# Mini51.net
KiCad netlist of a schematic drawn in Altium Designer
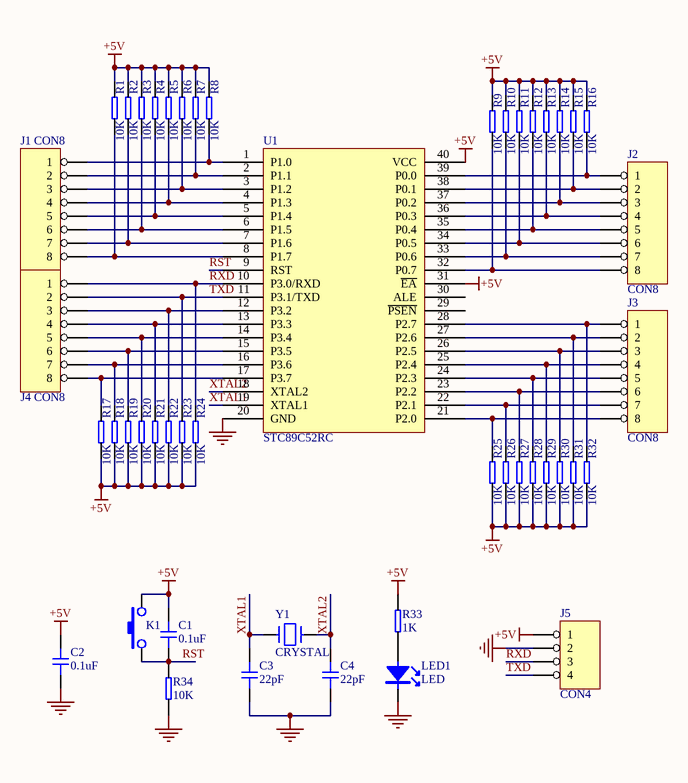
[diagram p0: Mini51.SchDoc]

(export (version "E")
  (design (tool "Eeschema 10.0.6"))
  (components
    (comp (ref "C1") (value "0.1uF") (footprint "0805") (libsource (lib "Mini51Lib") (part "CAP")))
    (comp (ref "C2") (value "0.1uF") (footprint "0805") (libsource (lib "Mini51Lib") (part "CAP")))
    (comp (ref "C3") (value "22pF") (footprint "0805") (libsource (lib "Mini51Lib") (part "CAP")))
    (comp (ref "C4") (value "22pF") (footprint "0805") (libsource (lib "Mini51Lib") (part "CAP")))
    (comp (ref "J1")
      (value "CON8")
      (footprint "SIP8")
      (description "Connector 8p")
      (libsource (lib "") (part "CON8_1"))
    )
    (comp (ref "J2")
      (value "CON8")
      (footprint "SIP8")
      (description "Connector 8p")
      (libsource (lib "Mini51Lib") (part "CON8"))
    )
    (comp (ref "J3")
      (value "CON8")
      (footprint "SIP8")
      (description "Connector 8p")
      (libsource (lib "Mini51Lib") (part "CON8"))
    )
    (comp (ref "J4")
      (value "CON8")
      (footprint "SIP8")
      (description "Connector 8p")
      (libsource (lib "") (part "CON8_1"))
    )
    (comp (ref "J5") (value "CON4") (footprint "SIP4") (libsource (lib "Mini51Lib") (part "CON4")))
    (comp (ref "K1")
      (value "KEY")
      (footprint "KEY-6*6")
      (description "push-button")
      (libsource (lib "Mini51Lib") (part "KEY"))
    )
    (comp (ref "LED1")
      (value "LED")
      (footprint "0805LD")
      (description "Light-Emitting Diode")
      (libsource (lib "Mini51Lib") (part "LED"))
    )
    (comp (ref "R1") (value "10K") (footprint "0805") (libsource (lib "Mini51Lib") (part "RES")))
    (comp (ref "R2") (value "10K") (footprint "0805") (libsource (lib "Mini51Lib") (part "RES")))
    (comp (ref "R3") (value "10K") (footprint "0805") (libsource (lib "Mini51Lib") (part "RES")))
    (comp (ref "R4") (value "10K") (footprint "0805") (libsource (lib "Mini51Lib") (part "RES")))
    (comp (ref "R5") (value "10K") (footprint "0805") (libsource (lib "Mini51Lib") (part "RES")))
    (comp (ref "R6") (value "10K") (footprint "0805") (libsource (lib "Mini51Lib") (part "RES")))
    (comp (ref "R7") (value "10K") (footprint "0805") (libsource (lib "Mini51Lib") (part "RES")))
    (comp (ref "R8") (value "10K") (footprint "0805") (libsource (lib "Mini51Lib") (part "RES")))
    (comp (ref "R9") (value "10K") (footprint "0805") (libsource (lib "Mini51Lib") (part "RES")))
    (comp (ref "R10") (value "10K") (footprint "0805") (libsource (lib "Mini51Lib") (part "RES")))
    (comp (ref "R11") (value "10K") (footprint "0805") (libsource (lib "Mini51Lib") (part "RES")))
    (comp (ref "R12") (value "10K") (footprint "0805") (libsource (lib "Mini51Lib") (part "RES")))
    (comp (ref "R13") (value "10K") (footprint "0805") (libsource (lib "Mini51Lib") (part "RES")))
    (comp (ref "R14") (value "10K") (footprint "0805") (libsource (lib "Mini51Lib") (part "RES")))
    (comp (ref "R15") (value "10K") (footprint "0805") (libsource (lib "Mini51Lib") (part "RES")))
    (comp (ref "R16") (value "10K") (footprint "0805") (libsource (lib "Mini51Lib") (part "RES")))
    (comp (ref "R17") (value "10K") (footprint "0805") (libsource (lib "Mini51Lib") (part "RES")))
    (comp (ref "R18") (value "10K") (footprint "0805") (libsource (lib "Mini51Lib") (part "RES")))
    (comp (ref "R19") (value "10K") (footprint "0805") (libsource (lib "Mini51Lib") (part "RES")))
    (comp (ref "R20") (value "10K") (footprint "0805") (libsource (lib "Mini51Lib") (part "RES")))
    (comp (ref "R21") (value "10K") (footprint "0805") (libsource (lib "Mini51Lib") (part "RES")))
    (comp (ref "R22") (value "10K") (footprint "0805") (libsource (lib "Mini51Lib") (part "RES")))
    (comp (ref "R23") (value "10K") (footprint "0805") (libsource (lib "Mini51Lib") (part "RES")))
    (comp (ref "R24") (value "10K") (footprint "0805") (libsource (lib "Mini51Lib") (part "RES")))
    (comp (ref "R25") (value "10K") (footprint "0805") (libsource (lib "Mini51Lib") (part "RES")))
    (comp (ref "R26") (value "10K") (footprint "0805") (libsource (lib "Mini51Lib") (part "RES")))
    (comp (ref "R27") (value "10K") (footprint "0805") (libsource (lib "Mini51Lib") (part "RES")))
    (comp (ref "R28") (value "10K") (footprint "0805") (libsource (lib "Mini51Lib") (part "RES")))
    (comp (ref "R29") (value "10K") (footprint "0805") (libsource (lib "Mini51Lib") (part "RES")))
    (comp (ref "R30") (value "10K") (footprint "0805") (libsource (lib "Mini51Lib") (part "RES")))
    (comp (ref "R31") (value "10K") (footprint "0805") (libsource (lib "Mini51Lib") (part "RES")))
    (comp (ref "R32") (value "10K") (footprint "0805") (libsource (lib "Mini51Lib") (part "RES")))
    (comp (ref "R33") (value "1K") (footprint "0805") (libsource (lib "Mini51Lib") (part "RES")))
    (comp (ref "R34") (value "10K") (footprint "0805") (libsource (lib "Mini51Lib") (part "RES")))
    (comp (ref "U1") (value "STC89C52RC") (footprint "DIP40") (libsource (lib "Mini51Lib") (part "STC89C52")))
    (comp (ref "Y1")
      (value "CRYSTAL")
      (footprint "XTAL-2")
      (description "Crystal")
      (libsource (lib "Mini51Lib") (part "CRYSTAL"))
    )
  )
  (nets
    (net (code "1") (name "+5V") (class "Default")
      (node (ref "C1") (pin "2") (pinfunction "2_2") (pintype "passive"))
      (node (ref "C2") (pin "2") (pinfunction "2_2") (pintype "passive"))
      (node (ref "J5") (pin "1") (pinfunction "1_1") (pintype "passive"))
      (node (ref "K1") (pin "2") (pinfunction "2_2") (pintype "passive"))
      (node (ref "R1") (pin "2") (pinfunction "2_2") (pintype "passive"))
      (node (ref "R10") (pin "2") (pinfunction "2_2") (pintype "passive"))
      (node (ref "R11") (pin "2") (pinfunction "2_2") (pintype "passive"))
      (node (ref "R12") (pin "2") (pinfunction "2_2") (pintype "passive"))
      (node (ref "R13") (pin "2") (pinfunction "2_2") (pintype "passive"))
      (node (ref "R14") (pin "2") (pinfunction "2_2") (pintype "passive"))
      (node (ref "R15") (pin "2") (pinfunction "2_2") (pintype "passive"))
      (node (ref "R16") (pin "2") (pinfunction "2_2") (pintype "passive"))
      (node (ref "R17") (pin "1") (pinfunction "1_1") (pintype "passive"))
      (node (ref "R18") (pin "1") (pinfunction "1_1") (pintype "passive"))
      (node (ref "R19") (pin "1") (pinfunction "1_1") (pintype "passive"))
      (node (ref "R2") (pin "2") (pinfunction "2_2") (pintype "passive"))
      (node (ref "R20") (pin "1") (pinfunction "1_1") (pintype "passive"))
      (node (ref "R21") (pin "1") (pinfunction "1_1") (pintype "passive"))
      (node (ref "R22") (pin "1") (pinfunction "1_1") (pintype "passive"))
      (node (ref "R23") (pin "1") (pinfunction "1_1") (pintype "passive"))
      (node (ref "R24") (pin "1") (pinfunction "1_1") (pintype "passive"))
      (node (ref "R25") (pin "1") (pinfunction "1_1") (pintype "passive"))
      (node (ref "R26") (pin "1") (pinfunction "1_1") (pintype "passive"))
      (node (ref "R27") (pin "1") (pinfunction "1_1") (pintype "passive"))
      (node (ref "R28") (pin "1") (pinfunction "1_1") (pintype "passive"))
      (node (ref "R29") (pin "1") (pinfunction "1_1") (pintype "passive"))
      (node (ref "R3") (pin "2") (pinfunction "2_2") (pintype "passive"))
      (node (ref "R30") (pin "1") (pinfunction "1_1") (pintype "passive"))
      (node (ref "R31") (pin "1") (pinfunction "1_1") (pintype "passive"))
      (node (ref "R32") (pin "1") (pinfunction "1_1") (pintype "passive"))
      (node (ref "R33") (pin "2") (pinfunction "2_2") (pintype "passive"))
      (node (ref "R4") (pin "2") (pinfunction "2_2") (pintype "passive"))
      (node (ref "R5") (pin "2") (pinfunction "2_2") (pintype "passive"))
      (node (ref "R6") (pin "2") (pinfunction "2_2") (pintype "passive"))
      (node (ref "R7") (pin "2") (pinfunction "2_2") (pintype "passive"))
      (node (ref "R8") (pin "2") (pinfunction "2_2") (pintype "passive"))
      (node (ref "R9") (pin "2") (pinfunction "2_2") (pintype "passive"))
      (node (ref "U1") (pin "31") (pinfunction "~{EA}_31") (pintype "passive"))
      (node (ref "U1") (pin "40") (pinfunction "VCC_40") (pintype "passive"))
    )
    (net (code "2") (name "/RST") (class "Default")
      (node (ref "C1") (pin "1") (pinfunction "1_1") (pintype "passive"))
      (node (ref "K1") (pin "1") (pinfunction "1_1") (pintype "passive"))
      (node (ref "R34") (pin "2") (pinfunction "2_2") (pintype "passive"))
      (node (ref "U1") (pin "9") (pinfunction "RST_9") (pintype "passive"))
    )
    (net (code "3") (name "/RXD") (class "Default")
      (node (ref "J4") (pin "1") (pinfunction "1_1") (pintype "passive"))
      (node (ref "J5") (pin "3") (pinfunction "3_3") (pintype "passive"))
      (node (ref "R24") (pin "2") (pinfunction "2_2") (pintype "passive"))
      (node (ref "U1") (pin "10") (pinfunction "P3.0/RXD_10") (pintype "passive"))
    )
    (net (code "4") (name "/TXD") (class "Default")
      (node (ref "J4") (pin "2") (pinfunction "2_2") (pintype "passive"))
      (node (ref "J5") (pin "4") (pinfunction "4_4") (pintype "passive"))
      (node (ref "R23") (pin "2") (pinfunction "2_2") (pintype "passive"))
      (node (ref "U1") (pin "11") (pinfunction "P3.1/TXD_11") (pintype "passive"))
    )
    (net (code "5") (name "/XTAL1") (class "Default")
      (node (ref "C3") (pin "2") (pinfunction "2_2") (pintype "passive"))
      (node (ref "U1") (pin "19") (pinfunction "XTAL1_19") (pintype "passive"))
      (node (ref "Y1") (pin "1") (pinfunction "1_1") (pintype "passive"))
    )
    (net (code "6") (name "/XTAL2") (class "Default")
      (node (ref "C4") (pin "2") (pinfunction "2_2") (pintype "passive"))
      (node (ref "U1") (pin "18") (pinfunction "XTAL2_18") (pintype "passive"))
      (node (ref "Y1") (pin "2") (pinfunction "2_2") (pintype "passive"))
    )
    (net (code "7") (name "GND") (class "Default")
      (node (ref "C2") (pin "1") (pinfunction "1_1") (pintype "passive"))
      (node (ref "C3") (pin "1") (pinfunction "1_1") (pintype "passive"))
      (node (ref "C4") (pin "1") (pinfunction "1_1") (pintype "passive"))
      (node (ref "J5") (pin "2") (pinfunction "2_2") (pintype "passive"))
      (node (ref "LED1") (pin "K") (pinfunction "2_K") (pintype "passive"))
      (node (ref "R34") (pin "1") (pinfunction "1_1") (pintype "passive"))
      (node (ref "U1") (pin "20") (pinfunction "GND_20") (pintype "passive"))
    )
    (net (code "8") (name "Net-(LED1-1)") (class "Default")
      (node (ref "LED1") (pin "A") (pinfunction "1_A") (pintype "passive"))
      (node (ref "R33") (pin "1") (pinfunction "1_1") (pintype "passive"))
    )
    (net (code "9") (name "Net-(U1-P0.0)") (class "Default")
      (node (ref "J2") (pin "1") (pinfunction "1_1") (pintype "passive"))
      (node (ref "R16") (pin "1") (pinfunction "1_1") (pintype "passive"))
      (node (ref "U1") (pin "39") (pinfunction "P0.0_39") (pintype "passive"))
    )
    (net (code "10") (name "Net-(U1-P0.1)") (class "Default")
      (node (ref "J2") (pin "2") (pinfunction "2_2") (pintype "passive"))
      (node (ref "R15") (pin "1") (pinfunction "1_1") (pintype "passive"))
      (node (ref "U1") (pin "38") (pinfunction "P0.1_38") (pintype "passive"))
    )
    (net (code "11") (name "Net-(U1-P0.2)") (class "Default")
      (node (ref "J2") (pin "3") (pinfunction "3_3") (pintype "passive"))
      (node (ref "R14") (pin "1") (pinfunction "1_1") (pintype "passive"))
      (node (ref "U1") (pin "37") (pinfunction "P0.2_37") (pintype "passive"))
    )
    (net (code "12") (name "Net-(U1-P0.3)") (class "Default")
      (node (ref "J2") (pin "4") (pinfunction "4_4") (pintype "passive"))
      (node (ref "R13") (pin "1") (pinfunction "1_1") (pintype "passive"))
      (node (ref "U1") (pin "36") (pinfunction "P0.3_36") (pintype "passive"))
    )
    (net (code "13") (name "Net-(U1-P0.4)") (class "Default")
      (node (ref "J2") (pin "5") (pinfunction "5_5") (pintype "passive"))
      (node (ref "R12") (pin "1") (pinfunction "1_1") (pintype "passive"))
      (node (ref "U1") (pin "35") (pinfunction "P0.4_35") (pintype "passive"))
    )
    (net (code "14") (name "Net-(U1-P0.5)") (class "Default")
      (node (ref "J2") (pin "6") (pinfunction "6_6") (pintype "passive"))
      (node (ref "R11") (pin "1") (pinfunction "1_1") (pintype "passive"))
      (node (ref "U1") (pin "34") (pinfunction "P0.5_34") (pintype "passive"))
    )
    (net (code "15") (name "Net-(U1-P0.6)") (class "Default")
      (node (ref "J2") (pin "7") (pinfunction "7_7") (pintype "passive"))
      (node (ref "R10") (pin "1") (pinfunction "1_1") (pintype "passive"))
      (node (ref "U1") (pin "33") (pinfunction "P0.6_33") (pintype "passive"))
    )
    (net (code "16") (name "Net-(U1-P0.7)") (class "Default")
      (node (ref "J2") (pin "8") (pinfunction "8_8") (pintype "passive"))
      (node (ref "R9") (pin "1") (pinfunction "1_1") (pintype "passive"))
      (node (ref "U1") (pin "32") (pinfunction "P0.7_32") (pintype "passive"))
    )
    (net (code "17") (name "Net-(U1-P1.0)") (class "Default")
      (node (ref "J1") (pin "1") (pinfunction "1_1") (pintype "passive"))
      (node (ref "R8") (pin "1") (pinfunction "1_1") (pintype "passive"))
      (node (ref "U1") (pin "1") (pinfunction "P1.0_1") (pintype "passive"))
    )
    (net (code "18") (name "Net-(U1-P1.1)") (class "Default")
      (node (ref "J1") (pin "2") (pinfunction "2_2") (pintype "passive"))
      (node (ref "R7") (pin "1") (pinfunction "1_1") (pintype "passive"))
      (node (ref "U1") (pin "2") (pinfunction "P1.1_2") (pintype "passive"))
    )
    (net (code "19") (name "Net-(U1-P1.2)") (class "Default")
      (node (ref "J1") (pin "3") (pinfunction "3_3") (pintype "passive"))
      (node (ref "R6") (pin "1") (pinfunction "1_1") (pintype "passive"))
      (node (ref "U1") (pin "3") (pinfunction "P1.2_3") (pintype "passive"))
    )
    (net (code "20") (name "Net-(U1-P1.3)") (class "Default")
      (node (ref "J1") (pin "4") (pinfunction "4_4") (pintype "passive"))
      (node (ref "R5") (pin "1") (pinfunction "1_1") (pintype "passive"))
      (node (ref "U1") (pin "4") (pinfunction "P1.3_4") (pintype "passive"))
    )
    (net (code "21") (name "Net-(U1-P1.4)") (class "Default")
      (node (ref "J1") (pin "5") (pinfunction "5_5") (pintype "passive"))
      (node (ref "R4") (pin "1") (pinfunction "1_1") (pintype "passive"))
      (node (ref "U1") (pin "5") (pinfunction "P1.4_5") (pintype "passive"))
    )
    (net (code "22") (name "Net-(U1-P1.5)") (class "Default")
      (node (ref "J1") (pin "6") (pinfunction "6_6") (pintype "passive"))
      (node (ref "R3") (pin "1") (pinfunction "1_1") (pintype "passive"))
      (node (ref "U1") (pin "6") (pinfunction "P1.5_6") (pintype "passive"))
    )
    (net (code "23") (name "Net-(U1-P1.6)") (class "Default")
      (node (ref "J1") (pin "7") (pinfunction "7_7") (pintype "passive"))
      (node (ref "R2") (pin "1") (pinfunction "1_1") (pintype "passive"))
      (node (ref "U1") (pin "7") (pinfunction "P1.6_7") (pintype "passive"))
    )
    (net (code "24") (name "Net-(U1-P1.7)") (class "Default")
      (node (ref "J1") (pin "8") (pinfunction "8_8") (pintype "passive"))
      (node (ref "R1") (pin "1") (pinfunction "1_1") (pintype "passive"))
      (node (ref "U1") (pin "8") (pinfunction "P1.7_8") (pintype "passive"))
    )
    (net (code "25") (name "Net-(U1-P2.0)") (class "Default")
      (node (ref "J3") (pin "8") (pinfunction "8_8") (pintype "passive"))
      (node (ref "R25") (pin "2") (pinfunction "2_2") (pintype "passive"))
      (node (ref "U1") (pin "21") (pinfunction "P2.0_21") (pintype "passive"))
    )
    (net (code "26") (name "Net-(U1-P2.1)") (class "Default")
      (node (ref "J3") (pin "7") (pinfunction "7_7") (pintype "passive"))
      (node (ref "R26") (pin "2") (pinfunction "2_2") (pintype "passive"))
      (node (ref "U1") (pin "22") (pinfunction "P2.1_22") (pintype "passive"))
    )
    (net (code "27") (name "Net-(U1-P2.2)") (class "Default")
      (node (ref "J3") (pin "6") (pinfunction "6_6") (pintype "passive"))
      (node (ref "R27") (pin "2") (pinfunction "2_2") (pintype "passive"))
      (node (ref "U1") (pin "23") (pinfunction "P2.2_23") (pintype "passive"))
    )
    (net (code "28") (name "Net-(U1-P2.3)") (class "Default")
      (node (ref "J3") (pin "5") (pinfunction "5_5") (pintype "passive"))
      (node (ref "R28") (pin "2") (pinfunction "2_2") (pintype "passive"))
      (node (ref "U1") (pin "24") (pinfunction "P2.3_24") (pintype "passive"))
    )
    (net (code "29") (name "Net-(U1-P2.4)") (class "Default")
      (node (ref "J3") (pin "4") (pinfunction "4_4") (pintype "passive"))
      (node (ref "R29") (pin "2") (pinfunction "2_2") (pintype "passive"))
      (node (ref "U1") (pin "25") (pinfunction "P2.4_25") (pintype "passive"))
    )
    (net (code "30") (name "Net-(U1-P2.5)") (class "Default")
      (node (ref "J3") (pin "3") (pinfunction "3_3") (pintype "passive"))
      (node (ref "R30") (pin "2") (pinfunction "2_2") (pintype "passive"))
      (node (ref "U1") (pin "26") (pinfunction "P2.5_26") (pintype "passive"))
    )
    (net (code "31") (name "Net-(U1-P2.6)") (class "Default")
      (node (ref "J3") (pin "2") (pinfunction "2_2") (pintype "passive"))
      (node (ref "R31") (pin "2") (pinfunction "2_2") (pintype "passive"))
      (node (ref "U1") (pin "27") (pinfunction "P2.6_27") (pintype "passive"))
    )
    (net (code "32") (name "Net-(U1-P2.7)") (class "Default")
      (node (ref "J3") (pin "1") (pinfunction "1_1") (pintype "passive"))
      (node (ref "R32") (pin "2") (pinfunction "2_2") (pintype "passive"))
      (node (ref "U1") (pin "28") (pinfunction "P2.7_28") (pintype "passive"))
    )
    (net (code "33") (name "Net-(U1-P3.2)") (class "Default")
      (node (ref "J4") (pin "3") (pinfunction "3_3") (pintype "passive"))
      (node (ref "R22") (pin "2") (pinfunction "2_2") (pintype "passive"))
      (node (ref "U1") (pin "12") (pinfunction "P3.2_12") (pintype "passive"))
    )
    (net (code "34") (name "Net-(U1-P3.3)") (class "Default")
      (node (ref "J4") (pin "4") (pinfunction "4_4") (pintype "passive"))
      (node (ref "R21") (pin "2") (pinfunction "2_2") (pintype "passive"))
      (node (ref "U1") (pin "13") (pinfunction "P3.3_13") (pintype "passive"))
    )
    (net (code "35") (name "Net-(U1-P3.4)") (class "Default")
      (node (ref "J4") (pin "5") (pinfunction "5_5") (pintype "passive"))
      (node (ref "R20") (pin "2") (pinfunction "2_2") (pintype "passive"))
      (node (ref "U1") (pin "14") (pinfunction "P3.4_14") (pintype "passive"))
    )
    (net (code "36") (name "Net-(U1-P3.5)") (class "Default")
      (node (ref "J4") (pin "6") (pinfunction "6_6") (pintype "passive"))
      (node (ref "R19") (pin "2") (pinfunction "2_2") (pintype "passive"))
      (node (ref "U1") (pin "15") (pinfunction "P3.5_15") (pintype "passive"))
    )
    (net (code "37") (name "Net-(U1-P3.6)") (class "Default")
      (node (ref "J4") (pin "7") (pinfunction "7_7") (pintype "passive"))
      (node (ref "R18") (pin "2") (pinfunction "2_2") (pintype "passive"))
      (node (ref "U1") (pin "16") (pinfunction "P3.6_16") (pintype "passive"))
    )
    (net (code "38") (name "Net-(U1-P3.7)") (class "Default")
      (node (ref "J4") (pin "8") (pinfunction "8_8") (pintype "passive"))
      (node (ref "R17") (pin "2") (pinfunction "2_2") (pintype "passive"))
      (node (ref "U1") (pin "17") (pinfunction "P3.7_17") (pintype "passive"))
    )
    (net (code "39") (name "unconnected-(U1-ALE-Pad30)") (class "Default")
      (node (ref "U1") (pin "30") (pinfunction "ALE_30") (pintype "passive"))
    )
    (net (code "40") (name "unconnected-(U1-~{PSEN}-Pad29)") (class "Default")
      (node (ref "U1") (pin "29") (pinfunction "~{PSEN}_29") (pintype "passive"))
    )
  )
)
